# test-board.net
KiCad netlist of a schematic drawn in EAGLE
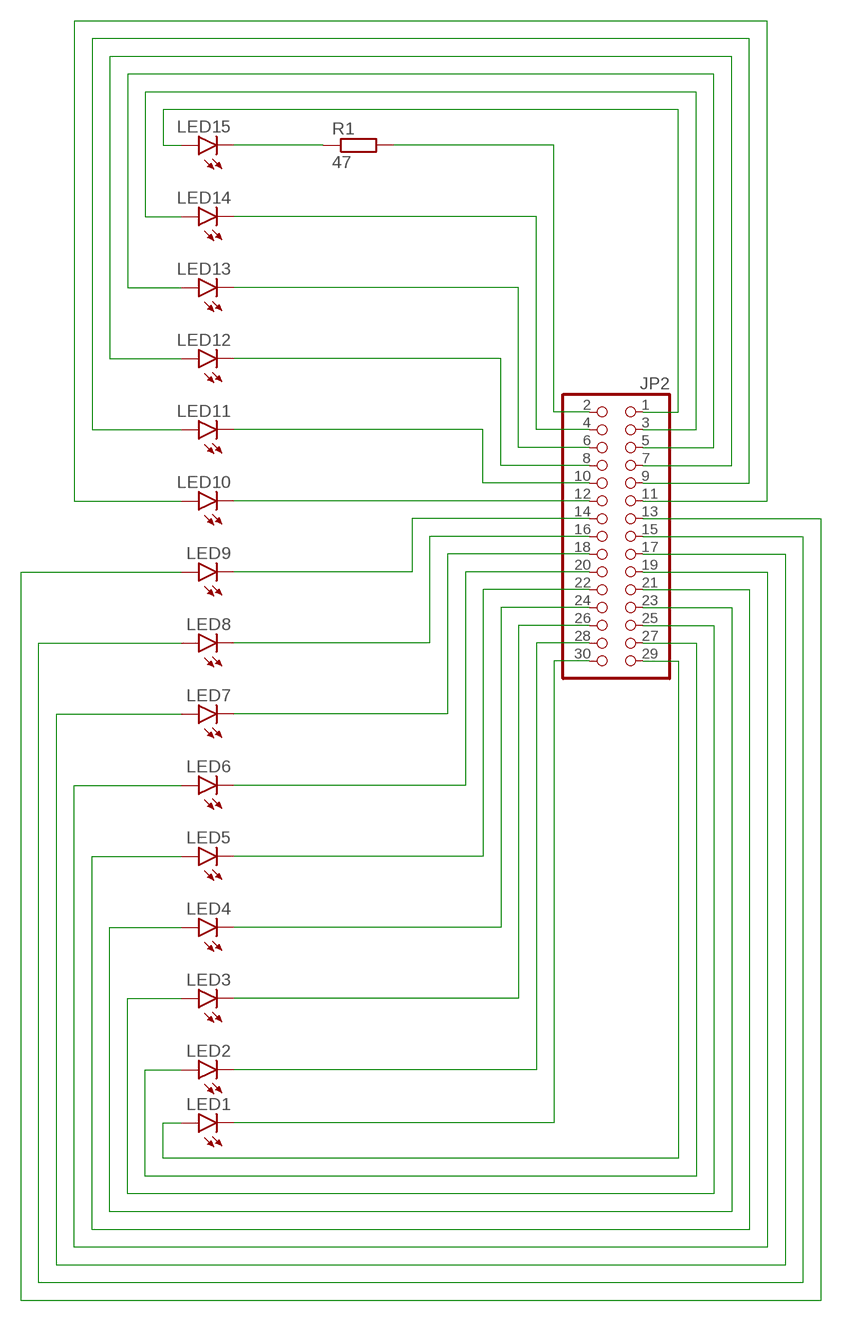
[diagram p0: schematic, sheet 1]

(export (version "E")
  (design (tool "Eeschema 10.0.6"))
  (components
    (comp (ref "JP2")
      (value "PINHD-2X15")
      (footprint "eagle-import:2X15")
      (libsource (lib "eagle-import") (part "PINHD-2X15"))
    )
    (comp (ref "LED1")
      (value "LED5MM")
      (footprint "eagle-import:LED5MM")
      (libsource (lib "eagle-import") (part "LED5MM"))
    )
    (comp (ref "LED2")
      (value "LED5MM")
      (footprint "eagle-import:LED5MM")
      (libsource (lib "eagle-import") (part "LED5MM"))
    )
    (comp (ref "LED3")
      (value "LED5MM")
      (footprint "eagle-import:LED5MM")
      (libsource (lib "eagle-import") (part "LED5MM"))
    )
    (comp (ref "LED4")
      (value "LED5MM")
      (footprint "eagle-import:LED5MM")
      (libsource (lib "eagle-import") (part "LED5MM"))
    )
    (comp (ref "LED5")
      (value "LED5MM")
      (footprint "eagle-import:LED5MM")
      (libsource (lib "eagle-import") (part "LED5MM"))
    )
    (comp (ref "LED6")
      (value "LED5MM")
      (footprint "eagle-import:LED5MM")
      (libsource (lib "eagle-import") (part "LED5MM"))
    )
    (comp (ref "LED7")
      (value "LED5MM")
      (footprint "eagle-import:LED5MM")
      (libsource (lib "eagle-import") (part "LED5MM"))
    )
    (comp (ref "LED8")
      (value "LED5MM")
      (footprint "eagle-import:LED5MM")
      (libsource (lib "eagle-import") (part "LED5MM"))
    )
    (comp (ref "LED9")
      (value "LED5MM")
      (footprint "eagle-import:LED5MM")
      (libsource (lib "eagle-import") (part "LED5MM"))
    )
    (comp (ref "LED10")
      (value "LED5MM")
      (footprint "eagle-import:LED5MM")
      (libsource (lib "eagle-import") (part "LED5MM"))
    )
    (comp (ref "LED11")
      (value "LED5MM")
      (footprint "eagle-import:LED5MM")
      (libsource (lib "eagle-import") (part "LED5MM"))
    )
    (comp (ref "LED12")
      (value "LED5MM")
      (footprint "eagle-import:LED5MM")
      (libsource (lib "eagle-import") (part "LED5MM"))
    )
    (comp (ref "LED13")
      (value "LED5MM")
      (footprint "eagle-import:LED5MM")
      (libsource (lib "eagle-import") (part "LED5MM"))
    )
    (comp (ref "LED14")
      (value "LED5MM")
      (footprint "eagle-import:LED5MM")
      (libsource (lib "eagle-import") (part "LED5MM"))
    )
    (comp (ref "LED15")
      (value "LED5MM")
      (footprint "eagle-import:LED5MM")
      (libsource (lib "eagle-import") (part "LED5MM"))
    )
    (comp (ref "R1")
      (value "47")
      (footprint "eagle-import:0207_10")
      (libsource (lib "eagle-import") (part "R-EU_0207/10"))
    )
  )
  (nets
    (net (code "1") (name "Net-(JP2-Pad1)") (class "Default")
      (node (ref "JP2") (pin "1") (pinfunction "1_1") (pintype "passive"))
      (node (ref "LED15") (pin "A") (pinfunction "A_A") (pintype "passive"))
    )
    (net (code "2") (name "Net-(JP2-Pad2)") (class "Default")
      (node (ref "JP2") (pin "2") (pinfunction "2_2") (pintype "passive"))
      (node (ref "R1") (pin "2") (pinfunction "2_2") (pintype "passive"))
    )
    (net (code "3") (name "Net-(JP2-Pad3)") (class "Default")
      (node (ref "JP2") (pin "3") (pinfunction "3_3") (pintype "passive"))
      (node (ref "LED14") (pin "A") (pinfunction "A_A") (pintype "passive"))
    )
    (net (code "4") (name "Net-(JP2-Pad5)") (class "Default")
      (node (ref "JP2") (pin "5") (pinfunction "5_5") (pintype "passive"))
      (node (ref "LED13") (pin "A") (pinfunction "A_A") (pintype "passive"))
    )
    (net (code "5") (name "Net-(JP2-Pad7)") (class "Default")
      (node (ref "JP2") (pin "7") (pinfunction "7_7") (pintype "passive"))
      (node (ref "LED12") (pin "A") (pinfunction "A_A") (pintype "passive"))
    )
    (net (code "6") (name "Net-(JP2-Pad9)") (class "Default")
      (node (ref "JP2") (pin "9") (pinfunction "9_9") (pintype "passive"))
      (node (ref "LED11") (pin "A") (pinfunction "A_A") (pintype "passive"))
    )
    (net (code "7") (name "Net-(JP2-Pad11)") (class "Default")
      (node (ref "JP2") (pin "11") (pinfunction "11_11") (pintype "passive"))
      (node (ref "LED10") (pin "A") (pinfunction "A_A") (pintype "passive"))
    )
    (net (code "8") (name "Net-(JP2-Pad13)") (class "Default")
      (node (ref "JP2") (pin "13") (pinfunction "13_13") (pintype "passive"))
      (node (ref "LED9") (pin "A") (pinfunction "A_A") (pintype "passive"))
    )
    (net (code "9") (name "Net-(JP2-Pad15)") (class "Default")
      (node (ref "JP2") (pin "15") (pinfunction "15_15") (pintype "passive"))
      (node (ref "LED8") (pin "A") (pinfunction "A_A") (pintype "passive"))
    )
    (net (code "10") (name "Net-(JP2-Pad17)") (class "Default")
      (node (ref "JP2") (pin "17") (pinfunction "17_17") (pintype "passive"))
      (node (ref "LED7") (pin "A") (pinfunction "A_A") (pintype "passive"))
    )
    (net (code "11") (name "Net-(JP2-Pad19)") (class "Default")
      (node (ref "JP2") (pin "19") (pinfunction "19_19") (pintype "passive"))
      (node (ref "LED6") (pin "A") (pinfunction "A_A") (pintype "passive"))
    )
    (net (code "12") (name "Net-(JP2-Pad21)") (class "Default")
      (node (ref "JP2") (pin "21") (pinfunction "21_21") (pintype "passive"))
      (node (ref "LED5") (pin "A") (pinfunction "A_A") (pintype "passive"))
    )
    (net (code "13") (name "Net-(JP2-Pad23)") (class "Default")
      (node (ref "JP2") (pin "23") (pinfunction "23_23") (pintype "passive"))
      (node (ref "LED4") (pin "A") (pinfunction "A_A") (pintype "passive"))
    )
    (net (code "14") (name "Net-(JP2-Pad25)") (class "Default")
      (node (ref "JP2") (pin "25") (pinfunction "25_25") (pintype "passive"))
      (node (ref "LED3") (pin "A") (pinfunction "A_A") (pintype "passive"))
    )
    (net (code "15") (name "Net-(JP2-Pad27)") (class "Default")
      (node (ref "JP2") (pin "27") (pinfunction "27_27") (pintype "passive"))
      (node (ref "LED2") (pin "A") (pinfunction "A_A") (pintype "passive"))
    )
    (net (code "16") (name "Net-(JP2-Pad29)") (class "Default")
      (node (ref "JP2") (pin "29") (pinfunction "29_29") (pintype "passive"))
      (node (ref "LED1") (pin "A") (pinfunction "A_A") (pintype "passive"))
    )
    (net (code "17") (name "Net-(LED1-C)") (class "Default")
      (node (ref "JP2") (pin "30") (pinfunction "30_30") (pintype "passive"))
      (node (ref "LED1") (pin "K") (pinfunction "C_K") (pintype "passive"))
    )
    (net (code "18") (name "Net-(LED2-C)") (class "Default")
      (node (ref "JP2") (pin "28") (pinfunction "28_28") (pintype "passive"))
      (node (ref "LED2") (pin "K") (pinfunction "C_K") (pintype "passive"))
    )
    (net (code "19") (name "Net-(LED3-C)") (class "Default")
      (node (ref "JP2") (pin "26") (pinfunction "26_26") (pintype "passive"))
      (node (ref "LED3") (pin "K") (pinfunction "C_K") (pintype "passive"))
    )
    (net (code "20") (name "Net-(LED4-C)") (class "Default")
      (node (ref "JP2") (pin "24") (pinfunction "24_24") (pintype "passive"))
      (node (ref "LED4") (pin "K") (pinfunction "C_K") (pintype "passive"))
    )
    (net (code "21") (name "Net-(LED5-C)") (class "Default")
      (node (ref "JP2") (pin "22") (pinfunction "22_22") (pintype "passive"))
      (node (ref "LED5") (pin "K") (pinfunction "C_K") (pintype "passive"))
    )
    (net (code "22") (name "Net-(LED6-C)") (class "Default")
      (node (ref "JP2") (pin "20") (pinfunction "20_20") (pintype "passive"))
      (node (ref "LED6") (pin "K") (pinfunction "C_K") (pintype "passive"))
    )
    (net (code "23") (name "Net-(LED7-C)") (class "Default")
      (node (ref "JP2") (pin "18") (pinfunction "18_18") (pintype "passive"))
      (node (ref "LED7") (pin "K") (pinfunction "C_K") (pintype "passive"))
    )
    (net (code "24") (name "Net-(LED8-C)") (class "Default")
      (node (ref "JP2") (pin "16") (pinfunction "16_16") (pintype "passive"))
      (node (ref "LED8") (pin "K") (pinfunction "C_K") (pintype "passive"))
    )
    (net (code "25") (name "Net-(LED9-C)") (class "Default")
      (node (ref "JP2") (pin "14") (pinfunction "14_14") (pintype "passive"))
      (node (ref "LED9") (pin "K") (pinfunction "C_K") (pintype "passive"))
    )
    (net (code "26") (name "Net-(LED10-C)") (class "Default")
      (node (ref "JP2") (pin "12") (pinfunction "12_12") (pintype "passive"))
      (node (ref "LED10") (pin "K") (pinfunction "C_K") (pintype "passive"))
    )
    (net (code "27") (name "Net-(LED11-C)") (class "Default")
      (node (ref "JP2") (pin "10") (pinfunction "10_10") (pintype "passive"))
      (node (ref "LED11") (pin "K") (pinfunction "C_K") (pintype "passive"))
    )
    (net (code "28") (name "Net-(LED12-C)") (class "Default")
      (node (ref "JP2") (pin "8") (pinfunction "8_8") (pintype "passive"))
      (node (ref "LED12") (pin "K") (pinfunction "C_K") (pintype "passive"))
    )
    (net (code "29") (name "Net-(LED13-C)") (class "Default")
      (node (ref "JP2") (pin "6") (pinfunction "6_6") (pintype "passive"))
      (node (ref "LED13") (pin "K") (pinfunction "C_K") (pintype "passive"))
    )
    (net (code "30") (name "Net-(LED14-C)") (class "Default")
      (node (ref "JP2") (pin "4") (pinfunction "4_4") (pintype "passive"))
      (node (ref "LED14") (pin "K") (pinfunction "C_K") (pintype "passive"))
    )
    (net (code "31") (name "Net-(LED15-C)") (class "Default")
      (node (ref "LED15") (pin "K") (pinfunction "C_K") (pintype "passive"))
      (node (ref "R1") (pin "1") (pinfunction "1_1") (pintype "passive"))
    )
  )
)
